# Main.net
KiCad netlist of a schematic drawn in Altium Designer
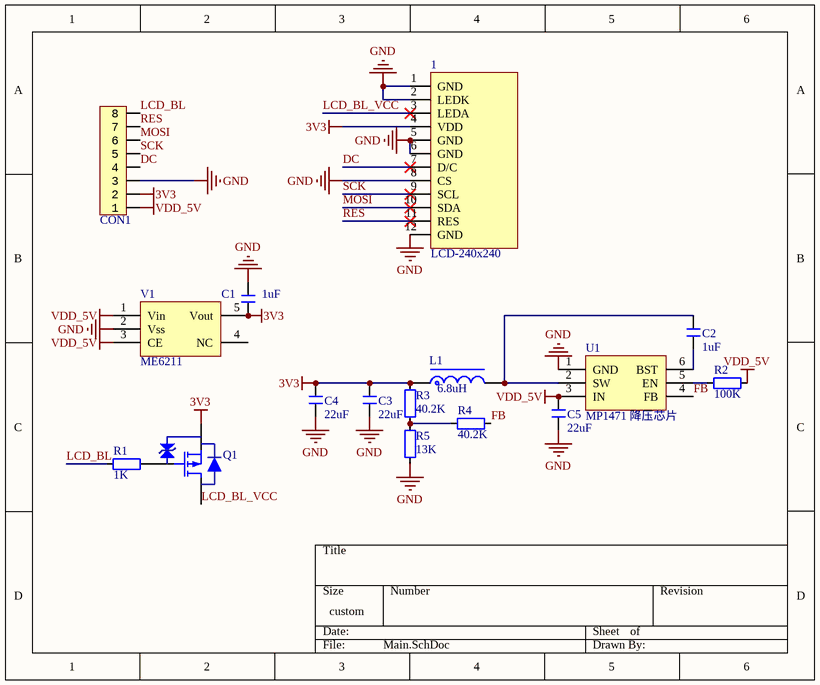
[diagram p0: Main.SchDoc]

(export (version "E")
  (design (tool "Eeschema 10.0.6"))
  (components
    (comp (ref "1")
      (value "LCD-240x240")
      (footprint "LCD-240x240-NoHole")
      (description "显示屏")
      (libsource (lib "ExtendBoard") (part "LCD-240x240"))
    )
    (comp (ref "C1")
      (value "1uF")
      (footprint "C 0402_L")
      (description "无极性贴片电容")
      (libsource (lib "ExtendBoard") (part "C"))
    )
    (comp (ref "C2")
      (value "1uF")
      (footprint "C 0402_L")
      (description "无极性贴片电容")
      (libsource (lib "ExtendBoard") (part "C"))
    )
    (comp (ref "C3")
      (value "22uF")
      (footprint "C 0805_L")
      (description "无极性贴片电容")
      (libsource (lib "ExtendBoard") (part "C"))
    )
    (comp (ref "C4")
      (value "22uF")
      (footprint "C 0805_L")
      (description "无极性贴片电容")
      (libsource (lib "ExtendBoard") (part "C"))
    )
    (comp (ref "C5")
      (value "22uF")
      (footprint "C 0805_L")
      (description "无极性贴片电容")
      (libsource (lib "ExtendBoard") (part "C"))
    )
    (comp (ref "CON1")
      (value "FFC_0.5_8")
      (footprint "FFC_0.5_8")
      (description "FFC")
      (libsource (lib "KitSprout") (part "FFC_0.5_8"))
    )
    (comp (ref "L1")
      (value "6.8uH")
      (footprint "NR4030")
      (description "NR磁胶电感")
      (libsource (lib "ExtendBoard") (part "L-NR"))
    )
    (comp (ref "Q1")
      (value "AO3415A")
      (footprint "SOT23-3")
      (description "MOSFET")
      (fields (field (name "PUBLISHER") "Altium Limited"))
      (libsource (lib "MyPcbLib") (part "AO3415A"))
    )
    (comp (ref "R1")
      (value "1K")
      (footprint "RES_0402")
      (description "Resistor")
      (libsource (lib "MyPcbLib") (part "电阻-0402"))
    )
    (comp (ref "R2")
      (value "100K")
      (footprint "RES_0402")
      (description "Resistor")
      (libsource (lib "") (part "电阻-0402_2"))
    )
    (comp (ref "R3")
      (value "40.2K")
      (footprint "RES_0402")
      (description "Resistor")
      (libsource (lib "") (part "电阻-0402_1"))
    )
    (comp (ref "R4")
      (value "40.2K")
      (footprint "RES_0402")
      (description "Resistor")
      (libsource (lib "") (part "电阻-0402_2"))
    )
    (comp (ref "R5")
      (value "13K")
      (footprint "RES_0402")
      (description "Resistor")
      (libsource (lib "ExtendBoard") (part "电阻-0402"))
    )
    (comp (ref "U1")
      (value "MP1471 降压芯片")
      (footprint "SOT23-6L")
      (description "DC降压芯片")
      (libsource (lib "ExtendBoard") (part "MP1471"))
    )
    (comp (ref "V1")
      (value "ME6211")
      (footprint "SOT23-5L")
      (description "低功耗LDO")
      (libsource (lib "ExtendBoard") (part "ME6211"))
    )
  )
  (nets
    (net (code "1") (name "/DC") (class "Default")
      (node (ref "1") (pin "7") (pinfunction "D/C_7") (pintype "passive"))
      (node (ref "CON1") (pin "4") (pinfunction "4_4") (pintype "passive"))
    )
    (net (code "2") (name "/FB") (class "Default")
      (node (ref "R4") (pin "2") (pinfunction "2_2") (pintype "passive"))
      (node (ref "U1") (pin "4") (pinfunction "FB_4") (pintype "passive"))
    )
    (net (code "3") (name "/LCD_BL") (class "Default")
      (node (ref "CON1") (pin "8") (pinfunction "8_8") (pintype "passive"))
      (node (ref "R1") (pin "1") (pinfunction "1_1") (pintype "passive"))
    )
    (net (code "4") (name "/LCD_BL_VCC") (class "Default")
      (node (ref "1") (pin "3") (pinfunction "LEDA_3") (pintype "passive"))
      (node (ref "Q1") (pin "3") (pinfunction "D_3") (pintype "passive"))
    )
    (net (code "5") (name "/MOSI") (class "Default")
      (node (ref "1") (pin "10") (pinfunction "SDA_10") (pintype "passive"))
      (node (ref "CON1") (pin "6") (pinfunction "6_6") (pintype "passive"))
    )
    (net (code "6") (name "/RES") (class "Default")
      (node (ref "1") (pin "11") (pinfunction "RES_11") (pintype "passive"))
      (node (ref "CON1") (pin "7") (pinfunction "7_7") (pintype "passive"))
    )
    (net (code "7") (name "/SCK") (class "Default")
      (node (ref "1") (pin "9") (pinfunction "SCL_9") (pintype "passive"))
      (node (ref "CON1") (pin "5") (pinfunction "5_5") (pintype "passive"))
    )
    (net (code "8") (name "3V3") (class "Default")
      (node (ref "1") (pin "4") (pinfunction "VDD_4") (pintype "passive"))
      (node (ref "C1") (pin "1") (pinfunction "1_1") (pintype "passive"))
      (node (ref "C3") (pin "2") (pinfunction "2_2") (pintype "passive"))
      (node (ref "C4") (pin "2") (pinfunction "2_2") (pintype "passive"))
      (node (ref "CON1") (pin "2") (pinfunction "2_2") (pintype "passive"))
      (node (ref "L1") (pin "1") (pinfunction "1_1") (pintype "passive"))
      (node (ref "Q1") (pin "2") (pinfunction "S_2") (pintype "passive"))
      (node (ref "R3") (pin "2") (pinfunction "2_2") (pintype "passive"))
      (node (ref "V1") (pin "5") (pinfunction "Vout_5") (pintype "passive"))
    )
    (net (code "9") (name "GND") (class "Default")
      (node (ref "1") (pin "1") (pinfunction "GND_1") (pintype "passive"))
      (node (ref "1") (pin "12") (pinfunction "GND_12") (pintype "passive"))
      (node (ref "1") (pin "2") (pinfunction "LEDK_2") (pintype "passive"))
      (node (ref "1") (pin "5") (pinfunction "GND_5") (pintype "passive"))
      (node (ref "1") (pin "6") (pinfunction "GND_6") (pintype "passive"))
      (node (ref "1") (pin "8") (pinfunction "CS_8") (pintype "passive"))
      (node (ref "C1") (pin "2") (pinfunction "2_2") (pintype "passive"))
      (node (ref "C3") (pin "1") (pinfunction "1_1") (pintype "passive"))
      (node (ref "C4") (pin "1") (pinfunction "1_1") (pintype "passive"))
      (node (ref "C5") (pin "1") (pinfunction "1_1") (pintype "passive"))
      (node (ref "CON1") (pin "3") (pinfunction "3_3") (pintype "passive"))
      (node (ref "R5") (pin "2") (pinfunction "2_2") (pintype "passive"))
      (node (ref "U1") (pin "1") (pinfunction "GND_1") (pintype "passive"))
      (node (ref "V1") (pin "2") (pinfunction "Vss_2") (pintype "passive"))
    )
    (net (code "10") (name "Net-(Q1-G)") (class "Default")
      (node (ref "Q1") (pin "1") (pinfunction "G_1") (pintype "passive"))
      (node (ref "R1") (pin "2") (pinfunction "2_2") (pintype "passive"))
    )
    (net (code "11") (name "Net-(R3-Pad1)") (class "Default")
      (node (ref "R3") (pin "1") (pinfunction "1_1") (pintype "passive"))
      (node (ref "R4") (pin "1") (pinfunction "1_1") (pintype "passive"))
      (node (ref "R5") (pin "1") (pinfunction "1_1") (pintype "passive"))
    )
    (net (code "12") (name "Net-(U1-BST)") (class "Default")
      (node (ref "C2") (pin "1") (pinfunction "1_1") (pintype "passive"))
      (node (ref "U1") (pin "6") (pinfunction "BST_6") (pintype "passive"))
    )
    (net (code "13") (name "Net-(U1-EN)") (class "Default")
      (node (ref "R2") (pin "1") (pinfunction "1_1") (pintype "passive"))
      (node (ref "U1") (pin "5") (pinfunction "EN_5") (pintype "passive"))
    )
    (net (code "14") (name "Net-(U1-SW)") (class "Default")
      (node (ref "C2") (pin "2") (pinfunction "2_2") (pintype "passive"))
      (node (ref "L1") (pin "2") (pinfunction "2_2") (pintype "passive"))
      (node (ref "U1") (pin "2") (pinfunction "SW_2") (pintype "passive"))
    )
    (net (code "15") (name "VDD_5V") (class "Default")
      (node (ref "C5") (pin "2") (pinfunction "2_2") (pintype "passive"))
      (node (ref "CON1") (pin "1") (pinfunction "1_1") (pintype "passive"))
      (node (ref "R2") (pin "2") (pinfunction "2_2") (pintype "passive"))
      (node (ref "U1") (pin "3") (pinfunction "IN_3") (pintype "passive"))
      (node (ref "V1") (pin "1") (pinfunction "Vin_1") (pintype "passive"))
      (node (ref "V1") (pin "3") (pinfunction "CE_3") (pintype "passive"))
    )
    (net (code "16") (name "unconnected-(V1-NC-Pad4)") (class "Default")
      (node (ref "V1") (pin "4") (pinfunction "NC_4") (pintype "passive"))
    )
  )
)
